# MagicDesk.net
KiCad netlist of a schematic drawn in EAGLE
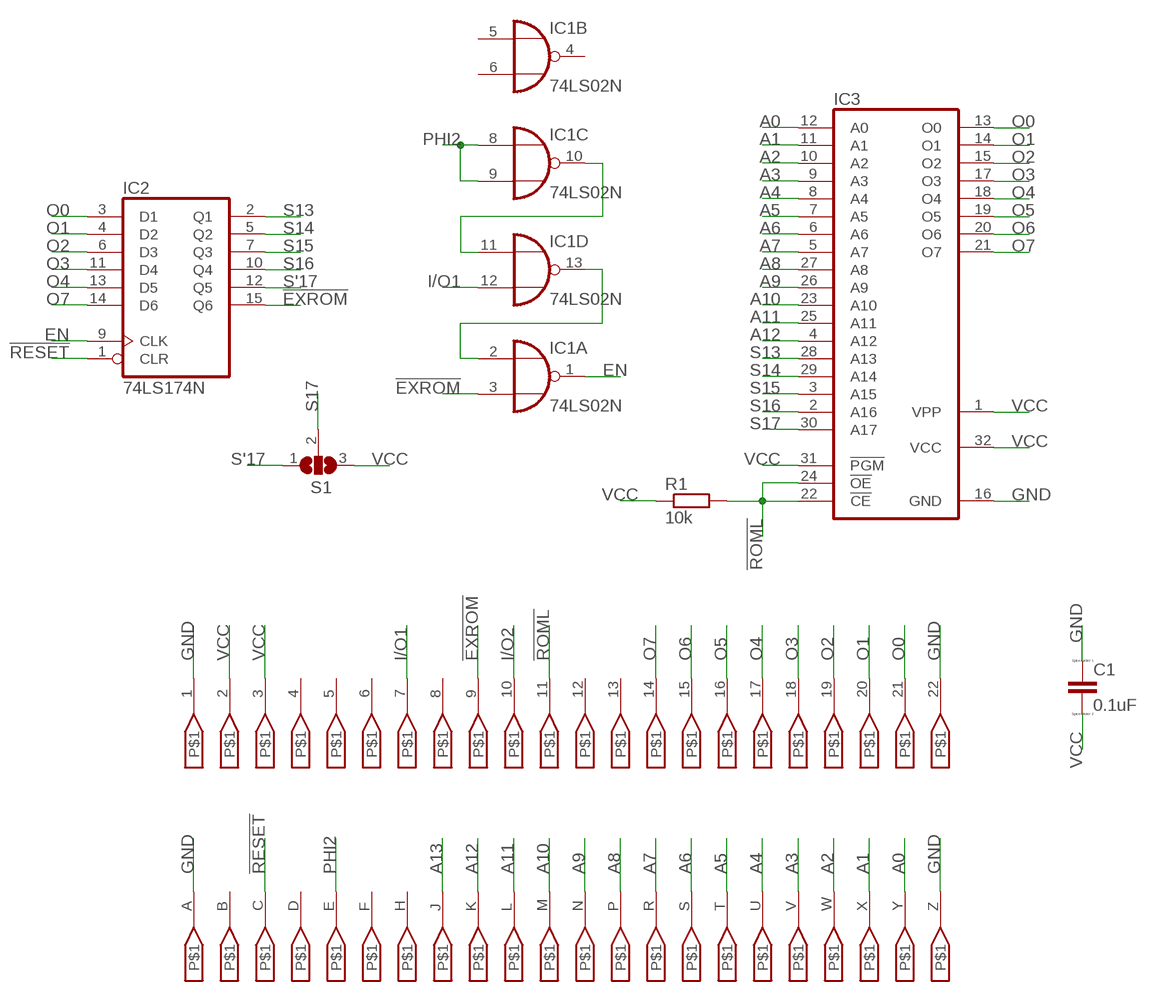
[diagram p0: schematic, sheet 1]

(export (version "E")
  (design (tool "Eeschema 10.0.6"))
  (components
    (comp (ref "C1")
      (value "0.1uF")
      (footprint "eagle-import:C050-24X044_SP")
      (libsource (lib "eagle-import") (part "C-EU050-24X044_SP"))
    )
    (comp (ref "IC1")
      (value "74LS02N")
      (footprint "eagle-import:DIL14")
      (libsource (lib "eagle-import") (part "7402NLS"))
    )
    (comp (ref "IC2")
      (value "74LS174N")
      (footprint "eagle-import:DIL16")
      (libsource (lib "eagle-import") (part "74174NLS"))
    )
    (comp (ref "IC3")
      (value "27C2001D")
      (footprint "eagle-import:DIL32")
      (fields (field (name "MPN") "M27C2001-10B1"))
      (libsource (lib "eagle-import") (part "27C2001D"))
    )
    (comp (ref "R1")
      (value "10k")
      (footprint "eagle-import:0207_10_SP")
      (libsource (lib "eagle-import") (part "R-EU_0207/10_SP"))
    )
    (comp (ref "S1")
      (value "SJ2W_NUMBERED")
      (footprint "eagle-import:SJ_2_NUM")
      (libsource (lib "eagle-import") (part "SJ2W_NUMBERED"))
    )
    (comp (ref "U$1")
      (value "C64_EXPANSION_FINGERS_PIN8X1.9")
      (footprint "eagle-import:C64_EXPANSION_FINGERS_THINNER")
      (libsource (lib "eagle-import") (part "C64_EXPANSION_FINGERS_PIN8X1.9"))
    )
  )
  (nets
    (net (code "1") (name "/A0") (class "Default")
      (node (ref "IC3") (pin "12") (pinfunction "A0_12") (pintype "input"))
      (node (ref "U$1") (pin "Y") (pinfunction "P$1_Y") (pintype "bidirectional"))
    )
    (net (code "2") (name "/A1") (class "Default")
      (node (ref "IC3") (pin "11") (pinfunction "A1_11") (pintype "input"))
      (node (ref "U$1") (pin "X") (pinfunction "P$1_X") (pintype "bidirectional"))
    )
    (net (code "3") (name "/A2") (class "Default")
      (node (ref "IC3") (pin "10") (pinfunction "A2_10") (pintype "input"))
      (node (ref "U$1") (pin "W") (pinfunction "P$1_W") (pintype "bidirectional"))
    )
    (net (code "4") (name "/A3") (class "Default")
      (node (ref "IC3") (pin "9") (pinfunction "A3_9") (pintype "input"))
      (node (ref "U$1") (pin "V") (pinfunction "P$1_V") (pintype "bidirectional"))
    )
    (net (code "5") (name "/A4") (class "Default")
      (node (ref "IC3") (pin "8") (pinfunction "A4_8") (pintype "input"))
      (node (ref "U$1") (pin "U") (pinfunction "P$1_U") (pintype "bidirectional"))
    )
    (net (code "6") (name "/A5") (class "Default")
      (node (ref "IC3") (pin "7") (pinfunction "A5_7") (pintype "input"))
      (node (ref "U$1") (pin "T") (pinfunction "P$1_T") (pintype "bidirectional"))
    )
    (net (code "7") (name "/A6") (class "Default")
      (node (ref "IC3") (pin "6") (pinfunction "A6_6") (pintype "input"))
      (node (ref "U$1") (pin "S") (pinfunction "P$1_S") (pintype "bidirectional"))
    )
    (net (code "8") (name "/A7") (class "Default")
      (node (ref "IC3") (pin "5") (pinfunction "A7_5") (pintype "input"))
      (node (ref "U$1") (pin "R") (pinfunction "P$1_R") (pintype "bidirectional"))
    )
    (net (code "9") (name "/A8") (class "Default")
      (node (ref "IC3") (pin "27") (pinfunction "A8_27") (pintype "input"))
      (node (ref "U$1") (pin "P") (pinfunction "P$1_P") (pintype "bidirectional"))
    )
    (net (code "10") (name "/A9") (class "Default")
      (node (ref "IC3") (pin "26") (pinfunction "A9_26") (pintype "input"))
      (node (ref "U$1") (pin "N") (pinfunction "P$1_N") (pintype "bidirectional"))
    )
    (net (code "11") (name "/A10") (class "Default")
      (node (ref "IC3") (pin "23") (pinfunction "A10_23") (pintype "input"))
      (node (ref "U$1") (pin "M") (pinfunction "P$1_M") (pintype "bidirectional"))
    )
    (net (code "12") (name "/A11") (class "Default")
      (node (ref "IC3") (pin "25") (pinfunction "A11_25") (pintype "input"))
      (node (ref "U$1") (pin "L") (pinfunction "P$1_L") (pintype "bidirectional"))
    )
    (net (code "13") (name "/A12") (class "Default")
      (node (ref "IC3") (pin "4") (pinfunction "A12_4") (pintype "input"))
      (node (ref "U$1") (pin "K") (pinfunction "P$1_K") (pintype "bidirectional"))
    )
    (net (code "14") (name "/A13") (class "Default")
      (node (ref "U$1") (pin "J") (pinfunction "P$1_J") (pintype "bidirectional"))
    )
    (net (code "15") (name "/EN") (class "Default")
      (node (ref "IC1") (pin "1") (pinfunction "O_1") (pintype "output"))
      (node (ref "IC2") (pin "9") (pinfunction "CLK_9") (pintype "input"))
    )
    (net (code "16") (name "/GND") (class "Default")
      (node (ref "C1") (pin "1") (pinfunction "1_1") (pintype "passive"))
      (node (ref "IC3") (pin "16") (pinfunction "GND_16") (pintype "power_in"))
      (node (ref "U$1") (pin "1") (pinfunction "P$1_1") (pintype "bidirectional"))
      (node (ref "U$1") (pin "22") (pinfunction "P$1_22") (pintype "bidirectional"))
      (node (ref "U$1") (pin "A") (pinfunction "P$1_A") (pintype "bidirectional"))
      (node (ref "U$1") (pin "Z") (pinfunction "P$1_Z") (pintype "bidirectional"))
    )
    (net (code "17") (name "/I{slash}O1") (class "Default")
      (node (ref "IC1") (pin "12") (pinfunction "I1_12") (pintype "input"))
      (node (ref "U$1") (pin "7") (pinfunction "P$1_7") (pintype "bidirectional"))
    )
    (net (code "18") (name "/I{slash}O2") (class "Default")
      (node (ref "U$1") (pin "10") (pinfunction "P$1_10") (pintype "bidirectional"))
    )
    (net (code "19") (name "/O0") (class "Default")
      (node (ref "IC2") (pin "3") (pinfunction "D1_3") (pintype "input"))
      (node (ref "IC3") (pin "13") (pinfunction "O0_13") (pintype "tri_state"))
      (node (ref "U$1") (pin "21") (pinfunction "P$1_21") (pintype "bidirectional"))
    )
    (net (code "20") (name "/O1") (class "Default")
      (node (ref "IC2") (pin "4") (pinfunction "D2_4") (pintype "input"))
      (node (ref "IC3") (pin "14") (pinfunction "O1_14") (pintype "tri_state"))
      (node (ref "U$1") (pin "20") (pinfunction "P$1_20") (pintype "bidirectional"))
    )
    (net (code "21") (name "/O2") (class "Default")
      (node (ref "IC2") (pin "6") (pinfunction "D3_6") (pintype "input"))
      (node (ref "IC3") (pin "15") (pinfunction "O2_15") (pintype "tri_state"))
      (node (ref "U$1") (pin "19") (pinfunction "P$1_19") (pintype "bidirectional"))
    )
    (net (code "22") (name "/O3") (class "Default")
      (node (ref "IC2") (pin "11") (pinfunction "D4_11") (pintype "input"))
      (node (ref "IC3") (pin "17") (pinfunction "O3_17") (pintype "tri_state"))
      (node (ref "U$1") (pin "18") (pinfunction "P$1_18") (pintype "bidirectional"))
    )
    (net (code "23") (name "/O4") (class "Default")
      (node (ref "IC2") (pin "13") (pinfunction "D5_13") (pintype "input"))
      (node (ref "IC3") (pin "18") (pinfunction "O4_18") (pintype "tri_state"))
      (node (ref "U$1") (pin "17") (pinfunction "P$1_17") (pintype "bidirectional"))
    )
    (net (code "24") (name "/O5") (class "Default")
      (node (ref "IC3") (pin "19") (pinfunction "O5_19") (pintype "tri_state"))
      (node (ref "U$1") (pin "16") (pinfunction "P$1_16") (pintype "bidirectional"))
    )
    (net (code "25") (name "/O6") (class "Default")
      (node (ref "IC3") (pin "20") (pinfunction "O6_20") (pintype "tri_state"))
      (node (ref "U$1") (pin "15") (pinfunction "P$1_15") (pintype "bidirectional"))
    )
    (net (code "26") (name "/O7") (class "Default")
      (node (ref "IC2") (pin "14") (pinfunction "D6_14") (pintype "input"))
      (node (ref "IC3") (pin "21") (pinfunction "O7_21") (pintype "tri_state"))
      (node (ref "U$1") (pin "14") (pinfunction "P$1_14") (pintype "bidirectional"))
    )
    (net (code "27") (name "/PHI2") (class "Default")
      (node (ref "IC1") (pin "8") (pinfunction "I0_8") (pintype "input"))
      (node (ref "IC1") (pin "9") (pinfunction "I1_9") (pintype "input"))
      (node (ref "U$1") (pin "E") (pinfunction "P$1_E") (pintype "bidirectional"))
    )
    (net (code "28") (name "/S'17") (class "Default")
      (node (ref "IC2") (pin "12") (pinfunction "Q5_12") (pintype "output"))
      (node (ref "S1") (pin "1") (pinfunction "1_1") (pintype "passive"))
    )
    (net (code "29") (name "/S13") (class "Default")
      (node (ref "IC2") (pin "2") (pinfunction "Q1_2") (pintype "output"))
      (node (ref "IC3") (pin "28") (pinfunction "A13_28") (pintype "input"))
    )
    (net (code "30") (name "/S14") (class "Default")
      (node (ref "IC2") (pin "5") (pinfunction "Q2_5") (pintype "output"))
      (node (ref "IC3") (pin "29") (pinfunction "A14_29") (pintype "input"))
    )
    (net (code "31") (name "/S15") (class "Default")
      (node (ref "IC2") (pin "7") (pinfunction "Q3_7") (pintype "output"))
      (node (ref "IC3") (pin "3") (pinfunction "A15_3") (pintype "input"))
    )
    (net (code "32") (name "/S16") (class "Default")
      (node (ref "IC2") (pin "10") (pinfunction "Q4_10") (pintype "output"))
      (node (ref "IC3") (pin "2") (pinfunction "A16_2") (pintype "input"))
    )
    (net (code "33") (name "/S17") (class "Default")
      (node (ref "IC3") (pin "30") (pinfunction "A17_30") (pintype "input"))
      (node (ref "S1") (pin "2") (pinfunction "2_2") (pintype "passive"))
    )
    (net (code "34") (name "/VCC") (class "Default")
      (node (ref "C1") (pin "2") (pinfunction "2_2") (pintype "passive"))
      (node (ref "IC3") (pin "1") (pinfunction "VPP_1") (pintype "passive"))
      (node (ref "IC3") (pin "31") (pinfunction "~{PGM}_31") (pintype "input"))
      (node (ref "IC3") (pin "32") (pinfunction "VCC_32") (pintype "power_in"))
      (node (ref "R1") (pin "1") (pinfunction "1_1") (pintype "passive"))
      (node (ref "S1") (pin "3") (pinfunction "3_3") (pintype "passive"))
      (node (ref "U$1") (pin "2") (pinfunction "P$1_2") (pintype "bidirectional"))
      (node (ref "U$1") (pin "3") (pinfunction "P$1_3") (pintype "bidirectional"))
    )
    (net (code "35") (name "/~{EXROM}") (class "Default")
      (node (ref "IC1") (pin "3") (pinfunction "I1_3") (pintype "input"))
      (node (ref "IC2") (pin "15") (pinfunction "Q6_15") (pintype "output"))
      (node (ref "U$1") (pin "9") (pinfunction "P$1_9") (pintype "bidirectional"))
    )
    (net (code "36") (name "/~{RESET}") (class "Default")
      (node (ref "IC2") (pin "1") (pinfunction "CLR_1") (pintype "input"))
      (node (ref "U$1") (pin "C") (pinfunction "P$1_C") (pintype "bidirectional"))
    )
    (net (code "37") (name "/~{ROML}") (class "Default")
      (node (ref "IC3") (pin "22") (pinfunction "~{CE}_22") (pintype "input"))
      (node (ref "IC3") (pin "24") (pinfunction "~{OE}_24") (pintype "input"))
      (node (ref "R1") (pin "2") (pinfunction "2_2") (pintype "passive"))
      (node (ref "U$1") (pin "11") (pinfunction "P$1_11") (pintype "bidirectional"))
    )
    (net (code "38") (name "Net-(IC1A-I0)") (class "Default")
      (node (ref "IC1") (pin "13") (pinfunction "O_13") (pintype "output"))
      (node (ref "IC1") (pin "2") (pinfunction "I0_2") (pintype "input"))
    )
    (net (code "39") (name "Net-(IC1C-O)") (class "Default")
      (node (ref "IC1") (pin "10") (pinfunction "O_10") (pintype "output"))
      (node (ref "IC1") (pin "11") (pinfunction "I0_11") (pintype "input"))
    )
    (net (code "40") (name "unconnected-(IC1B-I0-Pad5)") (class "Default")
      (node (ref "IC1") (pin "5") (pinfunction "I0_5") (pintype "input"))
    )
    (net (code "41") (name "unconnected-(IC1B-I1-Pad6)") (class "Default")
      (node (ref "IC1") (pin "6") (pinfunction "I1_6") (pintype "input"))
    )
    (net (code "42") (name "unconnected-(IC1B-O-Pad4)") (class "Default")
      (node (ref "IC1") (pin "4") (pinfunction "O_4") (pintype "output"))
    )
    (net (code "43") (name "unconnected-(U$1AH-P$1-Pad4)") (class "Default")
      (node (ref "U$1") (pin "4") (pinfunction "P$1_4") (pintype "bidirectional"))
    )
    (net (code "44") (name "unconnected-(U$1AN-P$1-Pad5)") (class "Default")
      (node (ref "U$1") (pin "5") (pinfunction "P$1_5") (pintype "bidirectional"))
    )
    (net (code "45") (name "unconnected-(U$1AO-P$1-Pad6)") (class "Default")
      (node (ref "U$1") (pin "6") (pinfunction "P$1_6") (pintype "bidirectional"))
    )
    (net (code "46") (name "unconnected-(U$1AQ-P$1-Pad8)") (class "Default")
      (node (ref "U$1") (pin "8") (pinfunction "P$1_8") (pintype "bidirectional"))
    )
    (net (code "47") (name "unconnected-(U$1D-P$1-Pad12)") (class "Default")
      (node (ref "U$1") (pin "12") (pinfunction "P$1_12") (pintype "bidirectional"))
    )
    (net (code "48") (name "unconnected-(U$1E-P$1-Pad13)") (class "Default")
      (node (ref "U$1") (pin "13") (pinfunction "P$1_13") (pintype "bidirectional"))
    )
    (net (code "49") (name "unconnected-(U$1Q-P$1-PadB)") (class "Default")
      (node (ref "U$1") (pin "B") (pinfunction "P$1_B") (pintype "bidirectional"))
    )
    (net (code "50") (name "unconnected-(U$1S-P$1-PadD)") (class "Default")
      (node (ref "U$1") (pin "D") (pinfunction "P$1_D") (pintype "bidirectional"))
    )
    (net (code "51") (name "unconnected-(U$1U-P$1-PadF)") (class "Default")
      (node (ref "U$1") (pin "F") (pinfunction "P$1_F") (pintype "bidirectional"))
    )
    (net (code "52") (name "unconnected-(U$1V-P$1-PadH)") (class "Default")
      (node (ref "U$1") (pin "H") (pinfunction "P$1_H") (pintype "bidirectional"))
    )
  )
)
